# 2_3c.net
KiCad netlist of a schematic drawn in EAGLE
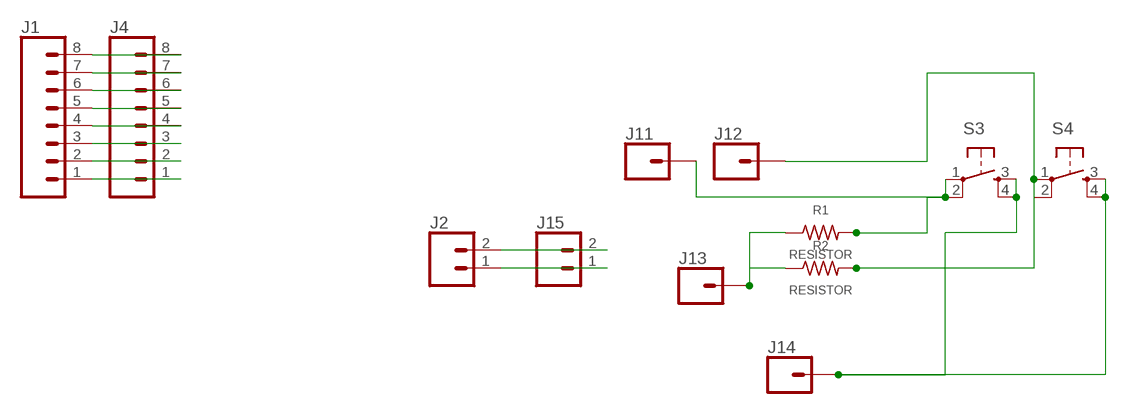
[diagram p0: schematic, sheet 1]

(export (version "E")
  (design (tool "Eeschema 10.0.6"))
  (components
    (comp (ref "J1")
      (value "CONN_08\"")
      (footprint "eagle-import:1X08")
      (libsource (lib "eagle-import") (part "CONN_08{dblquote}"))
    )
    (comp (ref "J2")
      (value "CONN_02")
      (footprint "eagle-import:1X02")
      (libsource (lib "eagle-import") (part "CONN_02"))
    )
    (comp (ref "J4")
      (value "CONN_08\"")
      (footprint "eagle-import:1X08")
      (libsource (lib "eagle-import") (part "CONN_08{dblquote}"))
    )
    (comp (ref "J11")
      (value "CONN_01")
      (footprint "eagle-import:1X01")
      (libsource (lib "eagle-import") (part "CONN_01"))
    )
    (comp (ref "J12")
      (value "CONN_01")
      (footprint "eagle-import:1X01")
      (libsource (lib "eagle-import") (part "CONN_01"))
    )
    (comp (ref "J13")
      (value "CONN_01")
      (footprint "eagle-import:1X01")
      (libsource (lib "eagle-import") (part "CONN_01"))
    )
    (comp (ref "J14")
      (value "CONN_01")
      (footprint "eagle-import:1X01")
      (libsource (lib "eagle-import") (part "CONN_01"))
    )
    (comp (ref "J15")
      (value "CONN_02")
      (footprint "eagle-import:1X02")
      (libsource (lib "eagle-import") (part "CONN_02"))
    )
    (comp (ref "R1")
      (value "RESISTOR")
      (footprint "eagle-import:0207_10")
      (libsource (lib "eagle-import") (part "RESISTOR"))
    )
    (comp (ref "R2")
      (value "RESISTOR")
      (footprint "eagle-import:0207_10")
      (libsource (lib "eagle-import") (part "RESISTOR"))
    )
    (comp (ref "S3")
      (value "TAC_SWITCHPTH")
      (footprint "eagle-import:TACTILE-PTH")
      (libsource (lib "eagle-import") (part "TAC_SWITCHPTH"))
    )
    (comp (ref "S4")
      (value "TAC_SWITCHPTH")
      (footprint "eagle-import:TACTILE-PTH")
      (libsource (lib "eagle-import") (part "TAC_SWITCHPTH"))
    )
  )
  (nets
    (net (code "1") (name "Net-(J1-Pad1)") (class "Default")
      (node (ref "J1") (pin "1") (pinfunction "1_1") (pintype "passive"))
      (node (ref "J4") (pin "1") (pinfunction "1_1") (pintype "passive"))
    )
    (net (code "2") (name "Net-(J1-Pad2)") (class "Default")
      (node (ref "J1") (pin "2") (pinfunction "2_2") (pintype "passive"))
      (node (ref "J4") (pin "2") (pinfunction "2_2") (pintype "passive"))
    )
    (net (code "3") (name "Net-(J1-Pad3)") (class "Default")
      (node (ref "J1") (pin "3") (pinfunction "3_3") (pintype "passive"))
      (node (ref "J4") (pin "3") (pinfunction "3_3") (pintype "passive"))
    )
    (net (code "4") (name "Net-(J1-Pad4)") (class "Default")
      (node (ref "J1") (pin "4") (pinfunction "4_4") (pintype "passive"))
      (node (ref "J4") (pin "4") (pinfunction "4_4") (pintype "passive"))
    )
    (net (code "5") (name "Net-(J1-Pad5)") (class "Default")
      (node (ref "J1") (pin "5") (pinfunction "5_5") (pintype "passive"))
      (node (ref "J4") (pin "5") (pinfunction "5_5") (pintype "passive"))
    )
    (net (code "6") (name "Net-(J1-Pad6)") (class "Default")
      (node (ref "J1") (pin "6") (pinfunction "6_6") (pintype "passive"))
      (node (ref "J4") (pin "6") (pinfunction "6_6") (pintype "passive"))
    )
    (net (code "7") (name "Net-(J1-Pad7)") (class "Default")
      (node (ref "J1") (pin "7") (pinfunction "7_7") (pintype "passive"))
      (node (ref "J4") (pin "7") (pinfunction "7_7") (pintype "passive"))
    )
    (net (code "8") (name "Net-(J1-Pad8)") (class "Default")
      (node (ref "J1") (pin "8") (pinfunction "8_8") (pintype "passive"))
      (node (ref "J4") (pin "8") (pinfunction "8_8") (pintype "passive"))
    )
    (net (code "9") (name "Net-(J11-Pad1)") (class "Default")
      (node (ref "J11") (pin "1") (pinfunction "1_1") (pintype "passive"))
      (node (ref "R1") (pin "2") (pinfunction "2_2") (pintype "passive"))
      (node (ref "S3") (pin "1") (pinfunction "1_1") (pintype "passive"))
      (node (ref "S3") (pin "2") (pinfunction "2_2") (pintype "passive"))
    )
    (net (code "10") (name "Net-(J12-Pad1)") (class "Default")
      (node (ref "J12") (pin "1") (pinfunction "1_1") (pintype "passive"))
      (node (ref "R2") (pin "2") (pinfunction "2_2") (pintype "passive"))
      (node (ref "S4") (pin "1") (pinfunction "1_1") (pintype "passive"))
      (node (ref "S4") (pin "2") (pinfunction "2_2") (pintype "passive"))
    )
    (net (code "11") (name "Net-(J13-Pad1)") (class "Default")
      (node (ref "J13") (pin "1") (pinfunction "1_1") (pintype "passive"))
      (node (ref "R1") (pin "1") (pinfunction "1_1") (pintype "passive"))
      (node (ref "R2") (pin "1") (pinfunction "1_1") (pintype "passive"))
    )
    (net (code "12") (name "Net-(J14-Pad1)") (class "Default")
      (node (ref "J14") (pin "1") (pinfunction "1_1") (pintype "passive"))
      (node (ref "S3") (pin "3") (pinfunction "3_3") (pintype "passive"))
      (node (ref "S3") (pin "4") (pinfunction "4_4") (pintype "passive"))
      (node (ref "S4") (pin "3") (pinfunction "3_3") (pintype "passive"))
      (node (ref "S4") (pin "4") (pinfunction "4_4") (pintype "passive"))
    )
    (net (code "13") (name "Net-(J15-Pad1)") (class "Default")
      (node (ref "J15") (pin "1") (pinfunction "1_1") (pintype "passive"))
      (node (ref "J2") (pin "1") (pinfunction "1_1") (pintype "passive"))
    )
    (net (code "14") (name "Net-(J15-Pad2)") (class "Default")
      (node (ref "J15") (pin "2") (pinfunction "2_2") (pintype "passive"))
      (node (ref "J2") (pin "2") (pinfunction "2_2") (pintype "passive"))
    )
  )
)
